# pump.net
KiCad netlist of a schematic drawn in EAGLE
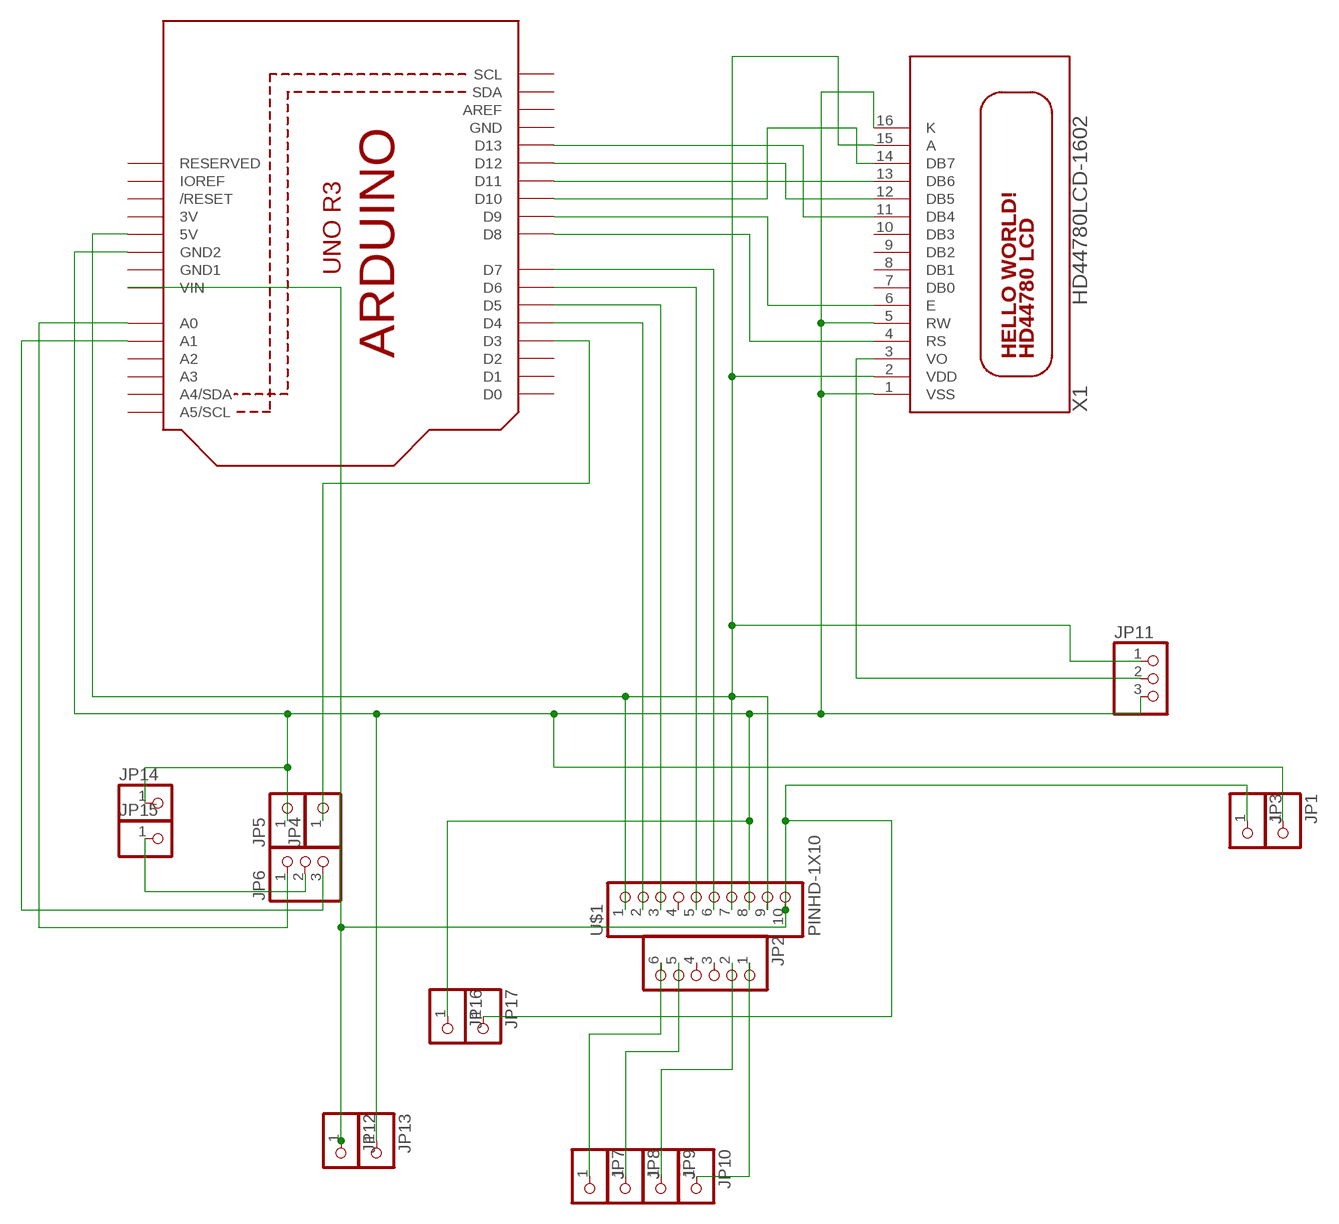
[diagram p0: schematic, sheet 1]

(export (version "E")
  (design (tool "Eeschema 10.0.6"))
  (components
    (comp (ref "JP1")
      (value "PINHD-1X1CB")
      (footprint "eagle-import:1X01-CLEANBIG")
      (libsource (lib "eagle-import") (part "PINHD-1X1CB"))
    )
    (comp (ref "JP2")
      (value "PINHD-1X6CB")
      (footprint "eagle-import:1X06-CLEANBIG")
      (libsource (lib "eagle-import") (part "PINHD-1X6CB"))
    )
    (comp (ref "JP3")
      (value "PINHD-1X1CB")
      (footprint "eagle-import:1X01-CLEANBIG")
      (libsource (lib "eagle-import") (part "PINHD-1X1CB"))
    )
    (comp (ref "JP4")
      (value "PINHD-1X1CB")
      (footprint "eagle-import:1X01-CLEANBIG")
      (libsource (lib "eagle-import") (part "PINHD-1X1CB"))
    )
    (comp (ref "JP5")
      (value "PINHD-1X1CB")
      (footprint "eagle-import:1X01-CLEANBIG")
      (libsource (lib "eagle-import") (part "PINHD-1X1CB"))
    )
    (comp (ref "JP6")
      (value "PINHD-1X3")
      (footprint "eagle-import:1X03")
      (libsource (lib "eagle-import") (part "PINHD-1X3"))
    )
    (comp (ref "JP7")
      (value "PINHD-1X1")
      (footprint "eagle-import:1X01")
      (libsource (lib "eagle-import") (part "PINHD-1X1"))
    )
    (comp (ref "JP8")
      (value "PINHD-1X1")
      (footprint "eagle-import:1X01")
      (libsource (lib "eagle-import") (part "PINHD-1X1"))
    )
    (comp (ref "JP9")
      (value "PINHD-1X1")
      (footprint "eagle-import:1X01")
      (libsource (lib "eagle-import") (part "PINHD-1X1"))
    )
    (comp (ref "JP10")
      (value "PINHD-1X1")
      (footprint "eagle-import:1X01")
      (libsource (lib "eagle-import") (part "PINHD-1X1"))
    )
    (comp (ref "JP11")
      (value "PINHD-1X3")
      (footprint "eagle-import:1X03")
      (libsource (lib "eagle-import") (part "PINHD-1X3"))
    )
    (comp (ref "JP12")
      (value "PINHD-1X1")
      (footprint "eagle-import:1X01")
      (libsource (lib "eagle-import") (part "PINHD-1X1"))
    )
    (comp (ref "JP13")
      (value "PINHD-1X1")
      (footprint "eagle-import:1X01")
      (libsource (lib "eagle-import") (part "PINHD-1X1"))
    )
    (comp (ref "JP14")
      (value "PINHD-1X1")
      (footprint "eagle-import:1X01")
      (libsource (lib "eagle-import") (part "PINHD-1X1"))
    )
    (comp (ref "JP15")
      (value "PINHD-1X1")
      (footprint "eagle-import:1X01")
      (libsource (lib "eagle-import") (part "PINHD-1X1"))
    )
    (comp (ref "JP16")
      (value "PINHD-1X1")
      (footprint "eagle-import:1X01")
      (libsource (lib "eagle-import") (part "PINHD-1X1"))
    )
    (comp (ref "JP17")
      (value "PINHD-1X1")
      (footprint "eagle-import:1X01")
      (libsource (lib "eagle-import") (part "PINHD-1X1"))
    )
    (comp (ref "U$1")
      (value "PINHD-1X10")
      (footprint "eagle-import:1X10-BIG")
      (libsource (lib "eagle-import") (part "PINHD-1X10"))
    )
    (comp (ref "U1")
      (value "ARDUINOR3-BPLACE")
      (footprint "eagle-import:ARDUINOR3-BPLACE")
      (libsource (lib "eagle-import") (part "ARDUINOR3-BPLACE"))
    )
    (comp (ref "X1")
      (value "HD44780LCD-1602")
      (footprint "eagle-import:LCD1602")
      (libsource (lib "eagle-import") (part "HD44780LCD-1602"))
    )
  )
  (nets
    (net (code "1") (name "/3V") (class "Default")
      (node (ref "U1") (pin "3V") (pinfunction "3V_3V") (pintype "power_in"))
    )
    (net (code "2") (name "/GND") (class "Default")
      (node (ref "U1") (pin "GND") (pinfunction "GND_GND") (pintype "power_in"))
    )
    (net (code "3") (name "/GND1") (class "Default")
      (node (ref "U1") (pin "GND1") (pinfunction "GND1_GND1") (pintype "power_in"))
    )
    (net (code "4") (name "Net-(JP2-Pad2)") (class "Default")
      (node (ref "JP2") (pin "2") (pinfunction "2_2") (pintype "passive"))
      (node (ref "JP9") (pin "1") (pinfunction "1_1") (pintype "passive"))
    )
    (net (code "5") (name "Net-(JP2-Pad5)") (class "Default")
      (node (ref "JP2") (pin "5") (pinfunction "5_5") (pintype "passive"))
      (node (ref "JP8") (pin "1") (pinfunction "1_1") (pintype "passive"))
    )
    (net (code "6") (name "Net-(JP2-Pad6)") (class "Default")
      (node (ref "JP2") (pin "6") (pinfunction "6_6") (pintype "passive"))
      (node (ref "JP7") (pin "1") (pinfunction "1_1") (pintype "passive"))
    )
    (net (code "7") (name "Net-(JP4-Pad1)") (class "Default")
      (node (ref "JP4") (pin "1") (pinfunction "1_1") (pintype "passive"))
      (node (ref "U1") (pin "D3") (pinfunction "D3_D3") (pintype "bidirectional"))
    )
    (net (code "8") (name "Net-(JP6-Pad1)") (class "Default")
      (node (ref "JP6") (pin "1") (pinfunction "1_1") (pintype "passive"))
      (node (ref "U1") (pin "A0") (pinfunction "A0_A0") (pintype "bidirectional"))
    )
    (net (code "9") (name "Net-(JP6-Pad3)") (class "Default")
      (node (ref "JP6") (pin "3") (pinfunction "3_3") (pintype "passive"))
      (node (ref "U1") (pin "A1") (pinfunction "A1_A1") (pintype "bidirectional"))
    )
    (net (code "10") (name "Net-(JP10-Pad1)") (class "Default")
      (node (ref "JP10") (pin "1") (pinfunction "1_1") (pintype "passive"))
      (node (ref "JP2") (pin "1") (pinfunction "1_1") (pintype "passive"))
    )
    (net (code "11") (name "Net-(JP12-Pad1)") (class "Default")
      (node (ref "JP12") (pin "1") (pinfunction "1_1") (pintype "passive"))
      (node (ref "JP17") (pin "1") (pinfunction "1_1") (pintype "passive"))
      (node (ref "JP3") (pin "1") (pinfunction "1_1") (pintype "passive"))
      (node (ref "U$1") (pin "10") (pinfunction "10_10") (pintype "passive"))
      (node (ref "U1") (pin "VIN") (pinfunction "VIN_VIN") (pintype "power_in"))
    )
    (net (code "12") (name "Net-(JP15-Pad1)") (class "Default")
      (node (ref "JP15") (pin "1") (pinfunction "1_1") (pintype "passive"))
      (node (ref "JP6") (pin "2") (pinfunction "2_2") (pintype "passive"))
    )
    (net (code "13") (name "Net-(U$1-Pad2)") (class "Default")
      (node (ref "U$1") (pin "2") (pinfunction "2_2") (pintype "passive"))
      (node (ref "U1") (pin "D4") (pinfunction "D4_D4") (pintype "bidirectional"))
    )
    (net (code "14") (name "Net-(U$1-Pad3)") (class "Default")
      (node (ref "U$1") (pin "3") (pinfunction "3_3") (pintype "passive"))
      (node (ref "U1") (pin "D5") (pinfunction "D5_D5") (pintype "bidirectional"))
    )
    (net (code "15") (name "Net-(U$1-Pad5)") (class "Default")
      (node (ref "U$1") (pin "5") (pinfunction "5_5") (pintype "passive"))
      (node (ref "U1") (pin "D6") (pinfunction "D6_D6") (pintype "bidirectional"))
    )
    (net (code "16") (name "Net-(U$1-Pad6)") (class "Default")
      (node (ref "U$1") (pin "6") (pinfunction "6_6") (pintype "passive"))
      (node (ref "U1") (pin "D7") (pinfunction "D7_D7") (pintype "bidirectional"))
    )
    (net (code "17") (name "Net-(X1-A)") (class "Default")
      (node (ref "JP11") (pin "1") (pinfunction "1_1") (pintype "passive"))
      (node (ref "U$1") (pin "1") (pinfunction "1_1") (pintype "passive"))
      (node (ref "U$1") (pin "7") (pinfunction "7_7") (pintype "passive"))
      (node (ref "U$1") (pin "9") (pinfunction "9_9") (pintype "passive"))
      (node (ref "U1") (pin "5V") (pinfunction "5V_5V") (pintype "power_in"))
      (node (ref "X1") (pin "15") (pinfunction "A_15") (pintype "input"))
      (node (ref "X1") (pin "2") (pinfunction "VDD_2") (pintype "power_in"))
    )
    (net (code "18") (name "Net-(X1-DB4)") (class "Default")
      (node (ref "U1") (pin "D13") (pinfunction "D13_D13") (pintype "bidirectional"))
      (node (ref "X1") (pin "11") (pinfunction "DB4_11") (pintype "bidirectional"))
    )
    (net (code "19") (name "Net-(X1-DB5)") (class "Default")
      (node (ref "U1") (pin "D12") (pinfunction "D12_D12") (pintype "bidirectional"))
      (node (ref "X1") (pin "12") (pinfunction "DB5_12") (pintype "bidirectional"))
    )
    (net (code "20") (name "Net-(X1-DB6)") (class "Default")
      (node (ref "U1") (pin "D11") (pinfunction "D11_D11") (pintype "bidirectional"))
      (node (ref "X1") (pin "13") (pinfunction "DB6_13") (pintype "bidirectional"))
    )
    (net (code "21") (name "Net-(X1-DB7)") (class "Default")
      (node (ref "U1") (pin "D10") (pinfunction "D10_D10") (pintype "bidirectional"))
      (node (ref "X1") (pin "14") (pinfunction "DB7_14") (pintype "bidirectional"))
    )
    (net (code "22") (name "Net-(X1-E)") (class "Default")
      (node (ref "U1") (pin "D9") (pinfunction "D9_D9") (pintype "bidirectional"))
      (node (ref "X1") (pin "6") (pinfunction "E_6") (pintype "input"))
    )
    (net (code "23") (name "Net-(X1-K)") (class "Default")
      (node (ref "JP1") (pin "1") (pinfunction "1_1") (pintype "passive"))
      (node (ref "JP11") (pin "3") (pinfunction "3_3") (pintype "passive"))
      (node (ref "JP13") (pin "1") (pinfunction "1_1") (pintype "passive"))
      (node (ref "JP14") (pin "1") (pinfunction "1_1") (pintype "passive"))
      (node (ref "JP16") (pin "1") (pinfunction "1_1") (pintype "passive"))
      (node (ref "JP5") (pin "1") (pinfunction "1_1") (pintype "passive"))
      (node (ref "U$1") (pin "8") (pinfunction "8_8") (pintype "passive"))
      (node (ref "U1") (pin "GND2") (pinfunction "GND2_GND2") (pintype "power_in"))
      (node (ref "X1") (pin "1") (pinfunction "VSS_1") (pintype "power_in"))
      (node (ref "X1") (pin "16") (pinfunction "K_16") (pintype "input"))
      (node (ref "X1") (pin "5") (pinfunction "RW_5") (pintype "input"))
    )
    (net (code "24") (name "Net-(X1-RS)") (class "Default")
      (node (ref "U1") (pin "D8") (pinfunction "D8_D8") (pintype "bidirectional"))
      (node (ref "X1") (pin "4") (pinfunction "RS_4") (pintype "input"))
    )
    (net (code "25") (name "Net-(X1-VO)") (class "Default")
      (node (ref "JP11") (pin "2") (pinfunction "2_2") (pintype "passive"))
      (node (ref "X1") (pin "3") (pinfunction "VO_3") (pintype "input"))
    )
    (net (code "26") (name "unconnected-(JP2-Pad3)") (class "Default")
      (node (ref "JP2") (pin "3") (pinfunction "3_3") (pintype "passive"))
    )
    (net (code "27") (name "unconnected-(JP2-Pad4)") (class "Default")
      (node (ref "JP2") (pin "4") (pinfunction "4_4") (pintype "passive"))
    )
    (net (code "28") (name "unconnected-(U$1-Pad4)") (class "Default")
      (node (ref "U$1") (pin "4") (pinfunction "4_4") (pintype "passive"))
    )
    (net (code "29") (name "unconnected-(U1-A4{slash}SDA-PadA4)") (class "Default")
      (node (ref "U1") (pin "A4") (pinfunction "A4/SDA_A4") (pintype "bidirectional"))
    )
    (net (code "30") (name "unconnected-(U1-A5{slash}SCL-PadA5)") (class "Default")
      (node (ref "U1") (pin "A5") (pinfunction "A5/SCL_A5") (pintype "bidirectional"))
    )
    (net (code "31") (name "unconnected-(U1-PadA2)") (class "Default")
      (node (ref "U1") (pin "A2") (pinfunction "A2_A2") (pintype "bidirectional"))
    )
    (net (code "32") (name "unconnected-(U1-PadA3)") (class "Default")
      (node (ref "U1") (pin "A3") (pinfunction "A3_A3") (pintype "bidirectional"))
    )
    (net (code "33") (name "unconnected-(U1-PadAREF)") (class "Default")
      (node (ref "U1") (pin "AREF") (pinfunction "AREF_AREF") (pintype "bidirectional"))
    )
    (net (code "34") (name "unconnected-(U1-PadD0)") (class "Default")
      (node (ref "U1") (pin "D0") (pinfunction "D0_D0") (pintype "bidirectional"))
    )
    (net (code "35") (name "unconnected-(U1-PadD1)") (class "Default")
      (node (ref "U1") (pin "D1") (pinfunction "D1_D1") (pintype "bidirectional"))
    )
    (net (code "36") (name "unconnected-(U1-PadD2)") (class "Default")
      (node (ref "U1") (pin "D2") (pinfunction "D2_D2") (pintype "bidirectional"))
    )
    (net (code "37") (name "unconnected-(U1-PadIOREF)") (class "Default")
      (node (ref "U1") (pin "IOREF") (pinfunction "IOREF_IOREF") (pintype "output"))
    )
    (net (code "38") (name "unconnected-(U1-PadRESERVED)") (class "Default")
      (node (ref "U1") (pin "RESERVED") (pinfunction "RESERVED_RESERVED") (pintype "no_connect"))
    )
    (net (code "39") (name "unconnected-(U1-PadSCL)") (class "Default")
      (node (ref "U1") (pin "SCL") (pinfunction "SCL_SCL") (pintype "bidirectional"))
    )
    (net (code "40") (name "unconnected-(U1-PadSDA)") (class "Default")
      (node (ref "U1") (pin "SDA") (pinfunction "SDA_SDA") (pintype "bidirectional"))
    )
    (net (code "41") (name "unconnected-(U1-{slash}RESET-PadRESET)") (class "Default")
      (node (ref "U1") (pin "RESET") (pinfunction "/RESET_RESET") (pintype "bidirectional"))
    )
    (net (code "42") (name "unconnected-(X1-DB0-Pad7)") (class "Default")
      (node (ref "X1") (pin "7") (pinfunction "DB0_7") (pintype "bidirectional"))
    )
    (net (code "43") (name "unconnected-(X1-DB1-Pad8)") (class "Default")
      (node (ref "X1") (pin "8") (pinfunction "DB1_8") (pintype "bidirectional"))
    )
    (net (code "44") (name "unconnected-(X1-DB2-Pad9)") (class "Default")
      (node (ref "X1") (pin "9") (pinfunction "DB2_9") (pintype "bidirectional"))
    )
    (net (code "45") (name "unconnected-(X1-DB3-Pad10)") (class "Default")
      (node (ref "X1") (pin "10") (pinfunction "DB3_10") (pintype "bidirectional"))
    )
  )
)
